# 02-CPU.net
KiCad netlist of a schematic drawn in Altium Designer
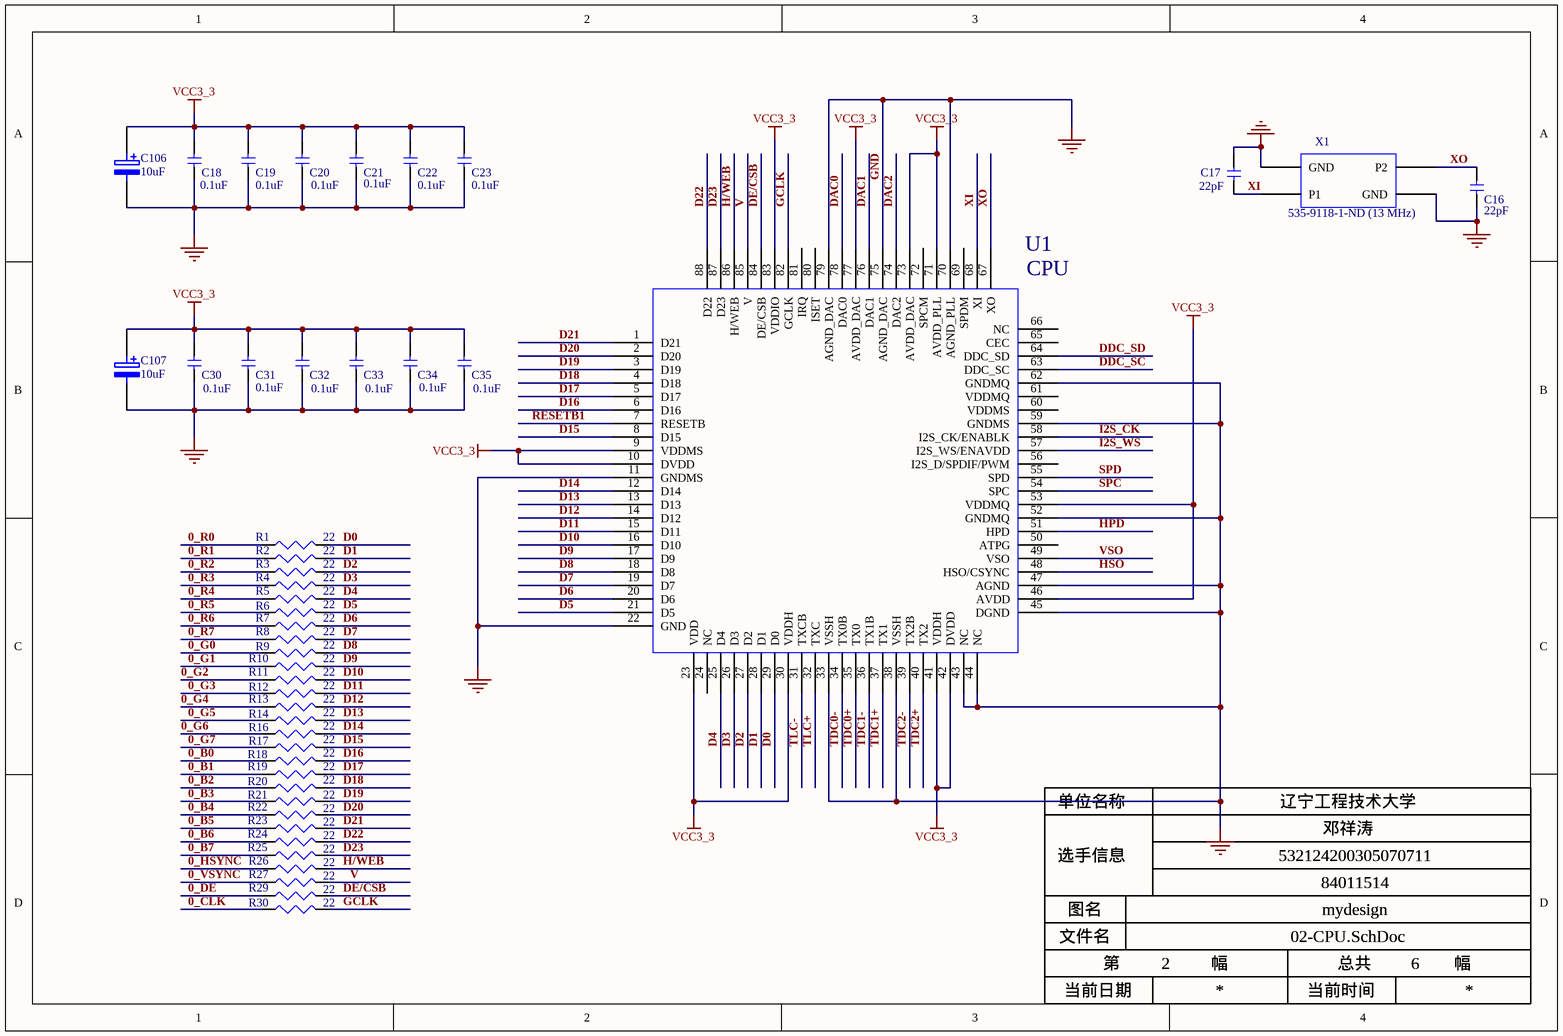
[diagram p0: 02-CPU.SchDoc]

(export (version "E")
  (design (tool "Eeschema 10.0.6"))
  (components
    (comp (ref "C16")
      (value "22pF")
      (footprint "C0603")
      (fields (field (name "VOLTAGE") "CMAX") (field (name "Comment") "C_2"))
      (libsource (lib "VIDEO_Demo_Kit_1") (part "C_2"))
    )
    (comp (ref "C17")
      (value "22pF")
      (footprint "C0603")
      (fields (field (name "VOLTAGE") "CMAX") (field (name "Comment") "C_2"))
      (libsource (lib "VIDEO_Demo_Kit_1") (part "C_2"))
    )
    (comp (ref "C18")
      (value "0.1uF")
      (footprint "C0603")
      (fields (field (name "VOLTAGE") "CMAX") (field (name "Comment") "C_2"))
      (libsource (lib "VIDEO_Demo_Kit_1") (part "C_2"))
    )
    (comp (ref "C19")
      (value "0.1uF")
      (footprint "C0603")
      (fields (field (name "VOLTAGE") "CMAX") (field (name "Comment") "C_2"))
      (libsource (lib "VIDEO_Demo_Kit_1") (part "C_2"))
    )
    (comp (ref "C20")
      (value "0.1uF")
      (footprint "C0603")
      (fields (field (name "VOLTAGE") "CMAX") (field (name "Comment") "C_2"))
      (libsource (lib "VIDEO_Demo_Kit_1") (part "C_2"))
    )
    (comp (ref "C21")
      (value "0.1uF")
      (footprint "C0603")
      (fields (field (name "VOLTAGE") "CMAX") (field (name "Comment") "C_2"))
      (libsource (lib "VIDEO_Demo_Kit_1") (part "C_2"))
    )
    (comp (ref "C22")
      (value "0.1uF")
      (footprint "C0603")
      (fields (field (name "VOLTAGE") "CMAX") (field (name "Comment") "C_2"))
      (libsource (lib "VIDEO_Demo_Kit_1") (part "C_2"))
    )
    (comp (ref "C23")
      (value "0.1uF")
      (footprint "C0603")
      (fields (field (name "VOLTAGE") "CMAX") (field (name "Comment") "C_2"))
      (libsource (lib "VIDEO_Demo_Kit_1") (part "C_2"))
    )
    (comp (ref "C30")
      (value "0.1uF")
      (footprint "C0603")
      (fields (field (name "VOLTAGE") "CMAX") (field (name "Comment") "C_2"))
      (libsource (lib "VIDEO_Demo_Kit_1") (part "C_2"))
    )
    (comp (ref "C31")
      (value "0.1uF")
      (footprint "C0603")
      (fields (field (name "VOLTAGE") "CMAX") (field (name "Comment") "C_2"))
      (libsource (lib "VIDEO_Demo_Kit_1") (part "C_2"))
    )
    (comp (ref "C32")
      (value "0.1uF")
      (footprint "C0603")
      (fields (field (name "VOLTAGE") "CMAX") (field (name "Comment") "C_2"))
      (libsource (lib "VIDEO_Demo_Kit_1") (part "C_2"))
    )
    (comp (ref "C33")
      (value "0.1uF")
      (footprint "C0603")
      (fields (field (name "VOLTAGE") "CMAX") (field (name "Comment") "C_2"))
      (libsource (lib "VIDEO_Demo_Kit_1") (part "C_2"))
    )
    (comp (ref "C34")
      (value "0.1uF")
      (footprint "C0603")
      (fields (field (name "VOLTAGE") "CMAX") (field (name "Comment") "C_2"))
      (libsource (lib "VIDEO_Demo_Kit_1") (part "C_2"))
    )
    (comp (ref "C35")
      (value "0.1uF")
      (footprint "C0603")
      (fields (field (name "VOLTAGE") "CMAX") (field (name "Comment") "C_2"))
      (libsource (lib "VIDEO_Demo_Kit_1") (part "C_2"))
    )
    (comp (ref "C106")
      (value "10uF")
      (footprint "3528-C")
      (description "Electrolytic Capacitor")
      (libsource (lib "*") (part "ELECTRO2"))
    )
    (comp (ref "C107")
      (value "10uF")
      (footprint "3528-C")
      (description "Electrolytic Capacitor")
      (libsource (lib "*") (part "ELECTRO2"))
    )
    (comp (ref "R1")
      (value "22")
      (footprint "R0603")
      (fields (field (name "Comment") "RESISTOR_2"))
      (libsource (lib "VIDEO_Demo_Kit_1") (part "RESISTOR_2"))
    )
    (comp (ref "R2")
      (value "22")
      (footprint "R0603")
      (fields (field (name "Comment") "RESISTOR_2"))
      (libsource (lib "VIDEO_Demo_Kit_1") (part "RESISTOR_2"))
    )
    (comp (ref "R3")
      (value "22")
      (footprint "R0603")
      (fields (field (name "Comment") "RESISTOR_2"))
      (libsource (lib "VIDEO_Demo_Kit_1") (part "RESISTOR_2"))
    )
    (comp (ref "R4")
      (value "22")
      (footprint "R0603")
      (fields (field (name "Comment") "RESISTOR_2"))
      (libsource (lib "VIDEO_Demo_Kit_1") (part "RESISTOR_2"))
    )
    (comp (ref "R5")
      (value "22")
      (footprint "R0603")
      (fields (field (name "Comment") "RESISTOR_2"))
      (libsource (lib "VIDEO_Demo_Kit_1") (part "RESISTOR_2"))
    )
    (comp (ref "R6")
      (value "22")
      (footprint "R0603")
      (fields (field (name "Comment") "RESISTOR_2"))
      (libsource (lib "VIDEO_Demo_Kit_1") (part "RESISTOR_2"))
    )
    (comp (ref "R7")
      (value "22")
      (footprint "R0603")
      (fields (field (name "Comment") "RESISTOR_2"))
      (libsource (lib "VIDEO_Demo_Kit_1") (part "RESISTOR_2"))
    )
    (comp (ref "R8")
      (value "22")
      (footprint "R0603")
      (fields (field (name "Comment") "RESISTOR_2"))
      (libsource (lib "VIDEO_Demo_Kit_1") (part "RESISTOR_2"))
    )
    (comp (ref "R9")
      (value "22")
      (footprint "R0603")
      (fields (field (name "Comment") "RESISTOR_2"))
      (libsource (lib "VIDEO_Demo_Kit_1") (part "RESISTOR_2"))
    )
    (comp (ref "R10")
      (value "22")
      (footprint "R0603")
      (fields (field (name "Comment") "RESISTOR_2"))
      (libsource (lib "VIDEO_Demo_Kit_1") (part "RESISTOR_2"))
    )
    (comp (ref "R11")
      (value "22")
      (footprint "R0603")
      (fields (field (name "Comment") "RESISTOR_2"))
      (libsource (lib "VIDEO_Demo_Kit_1") (part "RESISTOR_2"))
    )
    (comp (ref "R12")
      (value "22")
      (footprint "R0603")
      (fields (field (name "Comment") "RESISTOR_2"))
      (libsource (lib "VIDEO_Demo_Kit_1") (part "RESISTOR_2"))
    )
    (comp (ref "R13")
      (value "22")
      (footprint "R0603")
      (fields (field (name "Comment") "RESISTOR_2"))
      (libsource (lib "VIDEO_Demo_Kit_1") (part "RESISTOR_2"))
    )
    (comp (ref "R14")
      (value "22")
      (footprint "R0603")
      (fields (field (name "Comment") "RESISTOR_2"))
      (libsource (lib "VIDEO_Demo_Kit_1") (part "RESISTOR_2"))
    )
    (comp (ref "R16")
      (value "22")
      (footprint "R0603")
      (fields (field (name "Comment") "RESISTOR_2"))
      (libsource (lib "VIDEO_Demo_Kit_1") (part "RESISTOR_2"))
    )
    (comp (ref "R17")
      (value "22")
      (footprint "R0603")
      (fields (field (name "Comment") "RESISTOR_2"))
      (libsource (lib "VIDEO_Demo_Kit_1") (part "RESISTOR_2"))
    )
    (comp (ref "R18")
      (value "22")
      (footprint "R0603")
      (fields (field (name "Comment") "RESISTOR_2"))
      (libsource (lib "VIDEO_Demo_Kit_1") (part "RESISTOR_2"))
    )
    (comp (ref "R19")
      (value "22")
      (footprint "R0603")
      (fields (field (name "Comment") "RESISTOR_2"))
      (libsource (lib "VIDEO_Demo_Kit_1") (part "RESISTOR_2"))
    )
    (comp (ref "R20")
      (value "22")
      (footprint "R0603")
      (fields (field (name "Comment") "RESISTOR_2"))
      (libsource (lib "VIDEO_Demo_Kit_1") (part "RESISTOR_2"))
    )
    (comp (ref "R21")
      (value "22")
      (footprint "R0603")
      (fields (field (name "Comment") "RESISTOR_2"))
      (libsource (lib "VIDEO_Demo_Kit_1") (part "RESISTOR_2"))
    )
    (comp (ref "R22")
      (value "22")
      (footprint "R0603")
      (fields (field (name "Comment") "RESISTOR_2"))
      (libsource (lib "VIDEO_Demo_Kit_1") (part "RESISTOR_2"))
    )
    (comp (ref "R23")
      (value "22")
      (footprint "R0603")
      (fields (field (name "Comment") "RESISTOR_2"))
      (libsource (lib "VIDEO_Demo_Kit_1") (part "RESISTOR_2"))
    )
    (comp (ref "R24")
      (value "22")
      (footprint "R0603")
      (fields (field (name "Comment") "RESISTOR_2"))
      (libsource (lib "VIDEO_Demo_Kit_1") (part "RESISTOR_2"))
    )
    (comp (ref "R25")
      (value "22")
      (footprint "R0603")
      (fields (field (name "Comment") "RESISTOR_2"))
      (libsource (lib "VIDEO_Demo_Kit_1") (part "RESISTOR_2"))
    )
    (comp (ref "R26")
      (value "22")
      (footprint "R0603")
      (fields (field (name "Comment") "RESISTOR_2"))
      (libsource (lib "VIDEO_Demo_Kit_1") (part "RESISTOR_2"))
    )
    (comp (ref "R27")
      (value "22")
      (footprint "R0603")
      (fields (field (name "Comment") "RESISTOR_2"))
      (libsource (lib "VIDEO_Demo_Kit_1") (part "RESISTOR_2"))
    )
    (comp (ref "R29")
      (value "22")
      (footprint "R0603")
      (fields (field (name "Comment") "RESISTOR_2"))
      (libsource (lib "VIDEO_Demo_Kit_1") (part "RESISTOR_2"))
    )
    (comp (ref "R30")
      (value "22")
      (footprint "R0603")
      (fields (field (name "Comment") "RESISTOR_2"))
      (libsource (lib "VIDEO_Demo_Kit_1") (part "RESISTOR_2"))
    )
    (comp (ref "U1")
      (value "CPU")
      (footprint "QFN88")
      (fields
        (field (name "Comment") "LQFP80_5")
        (field (name "SOURCE_PATH") "C:\\DOCUME~1\\CAD01\\桌面\\TEST\\0622\\HDMI_B~1.DSN")
      )
      (libsource (lib "VIDEO_Demo_Kit") (part "LQFP80_5"))
    )
    (comp (ref "X1")
      (value "535-9118-1-ND (13 MHz)")
      (footprint "SMD-7050")
      (fields (field (name "Comment") "535-9118-1-ND"))
      (libsource (lib "*") (part "535-9118-1-ND"))
    )
  )
  (nets
    (net (code "1") (name "/0_B0") (class "Default")
      (node (ref "R18") (pin "1") (pinfunction "1_1") (pintype "passive"))
    )
    (net (code "2") (name "/0_B1") (class "Default")
      (node (ref "R19") (pin "1") (pinfunction "1_1") (pintype "passive"))
    )
    (net (code "3") (name "/0_B2") (class "Default")
      (node (ref "R20") (pin "1") (pinfunction "1_1") (pintype "passive"))
    )
    (net (code "4") (name "/0_B3") (class "Default")
      (node (ref "R21") (pin "1") (pinfunction "1_1") (pintype "passive"))
    )
    (net (code "5") (name "/0_B4") (class "Default")
      (node (ref "R22") (pin "1") (pinfunction "1_1") (pintype "passive"))
    )
    (net (code "6") (name "/0_B5") (class "Default")
      (node (ref "R23") (pin "1") (pinfunction "1_1") (pintype "passive"))
    )
    (net (code "7") (name "/0_B6") (class "Default")
      (node (ref "R24") (pin "1") (pinfunction "1_1") (pintype "passive"))
    )
    (net (code "8") (name "/0_B7") (class "Default")
      (node (ref "R25") (pin "1") (pinfunction "1_1") (pintype "passive"))
    )
    (net (code "9") (name "/0_CLK") (class "Default")
      (node (ref "R30") (pin "1") (pinfunction "1_1") (pintype "passive"))
    )
    (net (code "10") (name "/0_DE") (class "Default")
      (node (ref "R29") (pin "1") (pinfunction "1_1") (pintype "passive"))
    )
    (net (code "11") (name "/0_G0") (class "Default")
      (node (ref "R9") (pin "1") (pinfunction "1_1") (pintype "passive"))
    )
    (net (code "12") (name "/0_G1") (class "Default")
      (node (ref "R10") (pin "1") (pinfunction "1_1") (pintype "passive"))
    )
    (net (code "13") (name "/0_G2") (class "Default")
      (node (ref "R11") (pin "1") (pinfunction "1_1") (pintype "passive"))
    )
    (net (code "14") (name "/0_G3") (class "Default")
      (node (ref "R12") (pin "1") (pinfunction "1_1") (pintype "passive"))
    )
    (net (code "15") (name "/0_G4") (class "Default")
      (node (ref "R13") (pin "1") (pinfunction "1_1") (pintype "passive"))
    )
    (net (code "16") (name "/0_G5") (class "Default")
      (node (ref "R14") (pin "1") (pinfunction "1_1") (pintype "passive"))
    )
    (net (code "17") (name "/0_G6") (class "Default")
      (node (ref "R16") (pin "1") (pinfunction "1_1") (pintype "passive"))
    )
    (net (code "18") (name "/0_G7") (class "Default")
      (node (ref "R17") (pin "1") (pinfunction "1_1") (pintype "passive"))
    )
    (net (code "19") (name "/0_HSYNC") (class "Default")
      (node (ref "R26") (pin "1") (pinfunction "1_1") (pintype "passive"))
    )
    (net (code "20") (name "/0_R0") (class "Default")
      (node (ref "R1") (pin "1") (pinfunction "1_1") (pintype "passive"))
    )
    (net (code "21") (name "/0_R1") (class "Default")
      (node (ref "R2") (pin "1") (pinfunction "1_1") (pintype "passive"))
    )
    (net (code "22") (name "/0_R2") (class "Default")
      (node (ref "R3") (pin "1") (pinfunction "1_1") (pintype "passive"))
    )
    (net (code "23") (name "/0_R3") (class "Default")
      (node (ref "R4") (pin "1") (pinfunction "1_1") (pintype "passive"))
    )
    (net (code "24") (name "/0_R4") (class "Default")
      (node (ref "R5") (pin "1") (pinfunction "1_1") (pintype "passive"))
    )
    (net (code "25") (name "/0_R5") (class "Default")
      (node (ref "R6") (pin "1") (pinfunction "1_1") (pintype "passive"))
    )
    (net (code "26") (name "/0_R6") (class "Default")
      (node (ref "R7") (pin "1") (pinfunction "1_1") (pintype "passive"))
    )
    (net (code "27") (name "/0_R7") (class "Default")
      (node (ref "R8") (pin "1") (pinfunction "1_1") (pintype "passive"))
    )
    (net (code "28") (name "/0_VSYNC") (class "Default")
      (node (ref "R27") (pin "1") (pinfunction "1_1") (pintype "passive"))
    )
    (net (code "29") (name "/D0") (class "Default")
      (node (ref "R1") (pin "2") (pinfunction "2_2") (pintype "passive"))
      (node (ref "U1") (pin "29") (pinfunction "D0_29") (pintype "passive"))
    )
    (net (code "30") (name "/D1") (class "Default")
      (node (ref "R2") (pin "2") (pinfunction "2_2") (pintype "passive"))
      (node (ref "U1") (pin "28") (pinfunction "D1_28") (pintype "passive"))
    )
    (net (code "31") (name "/D2") (class "Default")
      (node (ref "R3") (pin "2") (pinfunction "2_2") (pintype "passive"))
      (node (ref "U1") (pin "27") (pinfunction "D2_27") (pintype "passive"))
    )
    (net (code "32") (name "/D3") (class "Default")
      (node (ref "R4") (pin "2") (pinfunction "2_2") (pintype "passive"))
      (node (ref "U1") (pin "26") (pinfunction "D3_26") (pintype "passive"))
    )
    (net (code "33") (name "/D4") (class "Default")
      (node (ref "R5") (pin "2") (pinfunction "2_2") (pintype "passive"))
      (node (ref "U1") (pin "25") (pinfunction "D4_25") (pintype "passive"))
    )
    (net (code "34") (name "/D5") (class "Default")
      (node (ref "R6") (pin "2") (pinfunction "2_2") (pintype "passive"))
      (node (ref "U1") (pin "21") (pinfunction "D5_21") (pintype "passive"))
    )
    (net (code "35") (name "/D6") (class "Default")
      (node (ref "R7") (pin "2") (pinfunction "2_2") (pintype "passive"))
      (node (ref "U1") (pin "20") (pinfunction "D6_20") (pintype "passive"))
    )
    (net (code "36") (name "/D7") (class "Default")
      (node (ref "R8") (pin "2") (pinfunction "2_2") (pintype "passive"))
      (node (ref "U1") (pin "19") (pinfunction "D7_19") (pintype "passive"))
    )
    (net (code "37") (name "/D8") (class "Default")
      (node (ref "R9") (pin "2") (pinfunction "2_2") (pintype "passive"))
      (node (ref "U1") (pin "18") (pinfunction "D8_18") (pintype "passive"))
    )
    (net (code "38") (name "/D9") (class "Default")
      (node (ref "R10") (pin "2") (pinfunction "2_2") (pintype "passive"))
      (node (ref "U1") (pin "17") (pinfunction "D9_17") (pintype "passive"))
    )
    (net (code "39") (name "/D10") (class "Default")
      (node (ref "R11") (pin "2") (pinfunction "2_2") (pintype "passive"))
      (node (ref "U1") (pin "16") (pinfunction "D10_16") (pintype "passive"))
    )
    (net (code "40") (name "/D11") (class "Default")
      (node (ref "R12") (pin "2") (pinfunction "2_2") (pintype "passive"))
      (node (ref "U1") (pin "15") (pinfunction "D11_15") (pintype "passive"))
    )
    (net (code "41") (name "/D12") (class "Default")
      (node (ref "R13") (pin "2") (pinfunction "2_2") (pintype "passive"))
      (node (ref "U1") (pin "14") (pinfunction "D12_14") (pintype "passive"))
    )
    (net (code "42") (name "/D13") (class "Default")
      (node (ref "R14") (pin "2") (pinfunction "2_2") (pintype "passive"))
      (node (ref "U1") (pin "13") (pinfunction "D13_13") (pintype "passive"))
    )
    (net (code "43") (name "/D14") (class "Default")
      (node (ref "R16") (pin "2") (pinfunction "2_2") (pintype "passive"))
      (node (ref "U1") (pin "12") (pinfunction "D14_12") (pintype "passive"))
    )
    (net (code "44") (name "/D15") (class "Default")
      (node (ref "R17") (pin "2") (pinfunction "2_2") (pintype "passive"))
      (node (ref "U1") (pin "8") (pinfunction "D15_8") (pintype "passive"))
    )
    (net (code "45") (name "/D16") (class "Default")
      (node (ref "R18") (pin "2") (pinfunction "2_2") (pintype "passive"))
      (node (ref "U1") (pin "6") (pinfunction "D16_6") (pintype "passive"))
    )
    (net (code "46") (name "/D17") (class "Default")
      (node (ref "R19") (pin "2") (pinfunction "2_2") (pintype "passive"))
      (node (ref "U1") (pin "5") (pinfunction "D17_5") (pintype "passive"))
    )
    (net (code "47") (name "/D18") (class "Default")
      (node (ref "R20") (pin "2") (pinfunction "2_2") (pintype "passive"))
      (node (ref "U1") (pin "4") (pinfunction "D18_4") (pintype "passive"))
    )
    (net (code "48") (name "/D19") (class "Default")
      (node (ref "R21") (pin "2") (pinfunction "2_2") (pintype "passive"))
      (node (ref "U1") (pin "3") (pinfunction "D19_3") (pintype "passive"))
    )
    (net (code "49") (name "/D20") (class "Default")
      (node (ref "R22") (pin "2") (pinfunction "2_2") (pintype "passive"))
      (node (ref "U1") (pin "2") (pinfunction "D20_2") (pintype "passive"))
    )
    (net (code "50") (name "/D21") (class "Default")
      (node (ref "R23") (pin "2") (pinfunction "2_2") (pintype "passive"))
      (node (ref "U1") (pin "1") (pinfunction "D21_1") (pintype "passive"))
    )
    (net (code "51") (name "/D22") (class "Default")
      (node (ref "R24") (pin "2") (pinfunction "2_2") (pintype "passive"))
      (node (ref "U1") (pin "88") (pinfunction "D22_88") (pintype "passive"))
    )
    (net (code "52") (name "/D23") (class "Default")
      (node (ref "R25") (pin "2") (pinfunction "2_2") (pintype "passive"))
      (node (ref "U1") (pin "87") (pinfunction "D23_87") (pintype "passive"))
    )
    (net (code "53") (name "/DAC0") (class "Default")
      (node (ref "U1") (pin "78") (pinfunction "DAC0_78") (pintype "passive"))
    )
    (net (code "54") (name "/DAC1") (class "Default")
      (node (ref "U1") (pin "76") (pinfunction "DAC1_76") (pintype "passive"))
    )
    (net (code "55") (name "/DAC2") (class "Default")
      (node (ref "U1") (pin "74") (pinfunction "DAC2_74") (pintype "passive"))
    )
    (net (code "56") (name "/DDC_SC") (class "Default")
      (node (ref "U1") (pin "63") (pinfunction "DDC_SC_63") (pintype "passive"))
    )
    (net (code "57") (name "/DDC_SD") (class "Default")
      (node (ref "U1") (pin "64") (pinfunction "DDC_SD_64") (pintype "passive"))
    )
    (net (code "58") (name "/DE{slash}CSB") (class "Default")
      (node (ref "R29") (pin "2") (pinfunction "2_2") (pintype "passive"))
      (node (ref "U1") (pin "84") (pinfunction "DE/CSB_84") (pintype "passive"))
    )
    (net (code "59") (name "/GCLK") (class "Default")
      (node (ref "R30") (pin "2") (pinfunction "2_2") (pintype "passive"))
      (node (ref "U1") (pin "82") (pinfunction "GCLK_82") (pintype "passive"))
    )
    (net (code "60") (name "/HPD") (class "Default")
      (node (ref "U1") (pin "51") (pinfunction "HPD_51") (pintype "passive"))
    )
    (net (code "61") (name "/HSO") (class "Default")
      (node (ref "U1") (pin "48") (pinfunction "HSO/CSYNC_48") (pintype "passive"))
    )
    (net (code "62") (name "/H{slash}WEB") (class "Default")
      (node (ref "R26") (pin "2") (pinfunction "2_2") (pintype "passive"))
      (node (ref "U1") (pin "86") (pinfunction "H/WEB_86") (pintype "passive"))
    )
    (net (code "63") (name "/I2S_CK") (class "Default")
      (node (ref "U1") (pin "58") (pinfunction "I2S_CK/ENABLK_58") (pintype "passive"))
    )
    (net (code "64") (name "/I2S_WS") (class "Default")
      (node (ref "U1") (pin "57") (pinfunction "I2S_WS/ENAVDD_57") (pintype "passive"))
    )
    (net (code "65") (name "/RESETB1") (class "Default")
      (node (ref "U1") (pin "7") (pinfunction "RESETB_7") (pintype "passive"))
    )
    (net (code "66") (name "/SPC") (class "Default")
      (node (ref "U1") (pin "54") (pinfunction "SPC_54") (pintype "passive"))
    )
    (net (code "67") (name "/SPD") (class "Default")
      (node (ref "U1") (pin "55") (pinfunction "SPD_55") (pintype "passive"))
    )
    (net (code "68") (name "/TDC0+") (class "Default")
      (node (ref "U1") (pin "35") (pinfunction "TX0_35") (pintype "passive"))
    )
    (net (code "69") (name "/TDC0-") (class "Default")
      (node (ref "U1") (pin "34") (pinfunction "TX0B_34") (pintype "passive"))
    )
    (net (code "70") (name "/TDC1+") (class "Default")
      (node (ref "U1") (pin "37") (pinfunction "TX1_37") (pintype "passive"))
    )
    (net (code "71") (name "/TDC1-") (class "Default")
      (node (ref "U1") (pin "36") (pinfunction "TX1B_36") (pintype "passive"))
    )
    (net (code "72") (name "/TDC2+") (class "Default")
      (node (ref "U1") (pin "40") (pinfunction "TX2_40") (pintype "passive"))
    )
    (net (code "73") (name "/TDC2-") (class "Default")
      (node (ref "U1") (pin "39") (pinfunction "TX2B_39") (pintype "passive"))
    )
    (net (code "74") (name "/TLC+") (class "Default")
      (node (ref "U1") (pin "32") (pinfunction "TXC_32") (pintype "passive"))
    )
    (net (code "75") (name "/TLC-") (class "Default")
      (node (ref "U1") (pin "31") (pinfunction "TXCB_31") (pintype "passive"))
    )
    (net (code "76") (name "/V") (class "Default")
      (node (ref "R27") (pin "2") (pinfunction "2_2") (pintype "passive"))
      (node (ref "U1") (pin "85") (pinfunction "V_85") (pintype "passive"))
    )
    (net (code "77") (name "/VSO") (class "Default")
      (node (ref "U1") (pin "49") (pinfunction "VSO_49") (pintype "passive"))
    )
    (net (code "78") (name "/XI") (class "Default")
      (node (ref "C17") (pin "2") (pinfunction "2_2") (pintype "passive"))
      (node (ref "U1") (pin "68") (pinfunction "XI_68") (pintype "passive"))
      (node (ref "X1") (pin "1") (pinfunction "P1_1") (pintype "passive"))
    )
    (net (code "79") (name "/XO") (class "Default")
      (node (ref "C16") (pin "2") (pinfunction "2_2") (pintype "passive"))
      (node (ref "U1") (pin "67") (pinfunction "XO_67") (pintype "passive"))
      (node (ref "X1") (pin "3") (pinfunction "P2_3") (pintype "passive"))
    )
    (net (code "80") (name "GND") (class "Default")
      (node (ref "C106") (pin "2") (pinfunction "2_2") (pintype "passive"))
      (node (ref "C107") (pin "2") (pinfunction "2_2") (pintype "passive"))
      (node (ref "C16") (pin "1") (pinfunction "1_1") (pintype "passive"))
      (node (ref "C17") (pin "1") (pinfunction "1_1") (pintype "passive"))
      (node (ref "C18") (pin "1") (pinfunction "1_1") (pintype "passive"))
      (node (ref "C19") (pin "1") (pinfunction "1_1") (pintype "passive"))
      (node (ref "C20") (pin "1") (pinfunction "1_1") (pintype "passive"))
      (node (ref "C21") (pin "1") (pinfunction "1_1") (pintype "passive"))
      (node (ref "C22") (pin "1") (pinfunction "1_1") (pintype "passive"))
      (node (ref "C23") (pin "1") (pinfunction "1_1") (pintype "passive"))
      (node (ref "C30") (pin "1") (pinfunction "1_1") (pintype "passive"))
      (node (ref "C31") (pin "1") (pinfunction "1_1") (pintype "passive"))
      (node (ref "C32") (pin "1") (pinfunction "1_1") (pintype "passive"))
      (node (ref "C33") (pin "1") (pinfunction "1_1") (pintype "passive"))
      (node (ref "C34") (pin "1") (pinfunction "1_1") (pintype "passive"))
      (node (ref "C35") (pin "1") (pinfunction "1_1") (pintype "passive"))
      (node (ref "U1") (pin "11") (pinfunction "GNDMS_11") (pintype "passive"))
      (node (ref "U1") (pin "22") (pinfunction "GND_22") (pintype "passive"))
      (node (ref "U1") (pin "33") (pinfunction "VSSH_33") (pintype "passive"))
      (node (ref "U1") (pin "38") (pinfunction "VSSH_38") (pintype "passive"))
      (node (ref "U1") (pin "43") (pinfunction "NC_43") (pintype "passive"))
      (node (ref "U1") (pin "44") (pinfunction "NC_44") (pintype "passive"))
      (node (ref "U1") (pin "45") (pinfunction "DGND_45") (pintype "passive"))
      (node (ref "U1") (pin "47") (pinfunction "AGND_47") (pintype "passive"))
      (node (ref "U1") (pin "52") (pinfunction "GNDMQ_52") (pintype "passive"))
      (node (ref "U1") (pin "59") (pinfunction "GNDMS_59") (pintype "passive"))
      (node (ref "U1") (pin "62") (pinfunction "GNDMQ_62") (pintype "passive"))
      (node (ref "U1") (pin "70") (pinfunction "AGND_PLL_70") (pintype "passive"))
      (node (ref "U1") (pin "75") (pinfunction "AGND_DAC_75") (pintype "passive"))
      (node (ref "U1") (pin "79") (pinfunction "AGND_DAC_79") (pintype "passive"))
      (node (ref "X1") (pin "2") (pinfunction "GND_2") (pintype "passive"))
      (node (ref "X1") (pin "4") (pinfunction "GND_4") (pintype "passive"))
    )
    (net (code "81") (name "VCC3_3") (class "Default")
      (node (ref "C106") (pin "1") (pinfunction "1_1") (pintype "passive"))
      (node (ref "C107") (pin "1") (pinfunction "1_1") (pintype "passive"))
      (node (ref "C18") (pin "2") (pinfunction "2_2") (pintype "passive"))
      (node (ref "C19") (pin "2") (pinfunction "2_2") (pintype "passive"))
      (node (ref "C20") (pin "2") (pinfunction "2_2") (pintype "passive"))
      (node (ref "C21") (pin "2") (pinfunction "2_2") (pintype "passive"))
      (node (ref "C22") (pin "2") (pinfunction "2_2") (pintype "passive"))
      (node (ref "C23") (pin "2") (pinfunction "2_2") (pintype "passive"))
      (node (ref "C30") (pin "2") (pinfunction "2_2") (pintype "passive"))
      (node (ref "C31") (pin "2") (pinfunction "2_2") (pintype "passive"))
      (node (ref "C32") (pin "2") (pinfunction "2_2") (pintype "passive"))
      (node (ref "C33") (pin "2") (pinfunction "2_2") (pintype "passive"))
      (node (ref "C34") (pin "2") (pinfunction "2_2") (pintype "passive"))
      (node (ref "C35") (pin "2") (pinfunction "2_2") (pintype "passive"))
      (node (ref "U1") (pin "10") (pinfunction "DVDD_10") (pintype "passive"))
      (node (ref "U1") (pin "23") (pinfunction "VDD_23") (pintype "passive"))
      (node (ref "U1") (pin "30") (pinfunction "VDDH_30") (pintype "passive"))
      (node (ref "U1") (pin "41") (pinfunction "VDDH_41") (pintype "passive"))
      (node (ref "U1") (pin "42") (pinfunction "DVDD_42") (pintype "passive"))
      (node (ref "U1") (pin "46") (pinfunction "AVDD_46") (pintype "passive"))
      (node (ref "U1") (pin "53") (pinfunction "VDDMQ_53") (pintype "passive"))
      (node (ref "U1") (pin "71") (pinfunction "AVDD_PLL_71") (pintype "passive"))
      (node (ref "U1") (pin "73") (pinfunction "AVDD_DAC_73") (pintype "passive"))
      (node (ref "U1") (pin "77") (pinfunction "AVDD_DAC_77") (pintype "passive"))
      (node (ref "U1") (pin "83") (pinfunction "VDDIO_83") (pintype "passive"))
      (node (ref "U1") (pin "9") (pinfunction "VDDMS_9") (pintype "passive"))
    )
    (net (code "82") (name "unconnected-(U1-ATPG-Pad50)") (class "Default")
      (node (ref "U1") (pin "50") (pinfunction "ATPG_50") (pintype "passive"))
    )
    (net (code "83") (name "unconnected-(U1-CEC-Pad65)") (class "Default")
      (node (ref "U1") (pin "65") (pinfunction "CEC_65") (pintype "passive"))
    )
    (net (code "84") (name "unconnected-(U1-I2S_D{slash}SPDIF{slash}PWM-Pad56)") (class "Default")
      (node (ref "U1") (pin "56") (pinfunction "I2S_D/SPDIF/PWM_56") (pintype "passive"))
    )
    (net (code "85") (name "unconnected-(U1-IRQ-Pad81)") (class "Default")
      (node (ref "U1") (pin "81") (pinfunction "IRQ_81") (pintype "passive"))
    )
    (net (code "86") (name "unconnected-(U1-ISET-Pad80)") (class "Default")
      (node (ref "U1") (pin "80") (pinfunction "ISET_80") (pintype "passive"))
    )
    (net (code "87") (name "unconnected-(U1-NC-Pad24)") (class "Default")
      (node (ref "U1") (pin "24") (pinfunction "NC_24") (pintype "passive"))
    )
    (net (code "88") (name "unconnected-(U1-NC-Pad66)") (class "Default")
      (node (ref "U1") (pin "66") (pinfunction "NC_66") (pintype "passive"))
    )
    (net (code "89") (name "unconnected-(U1-SPCM-Pad72)") (class "Default")
      (node (ref "U1") (pin "72") (pinfunction "SPCM_72") (pintype "passive"))
    )
    (net (code "90") (name "unconnected-(U1-SPDM-Pad69)") (class "Default")
      (node (ref "U1") (pin "69") (pinfunction "SPDM_69") (pintype "passive"))
    )
    (net (code "91") (name "unconnected-(U1-VDDMQ-Pad61)") (class "Default")
      (node (ref "U1") (pin "61") (pinfunction "VDDMQ_61") (pintype "passive"))
    )
    (net (code "92") (name "unconnected-(U1-VDDMS-Pad60)") (class "Default")
      (node (ref "U1") (pin "60") (pinfunction "VDDMS_60") (pintype "passive"))
    )
  )
)
